# 12-Dash_Inputs.net
KiCad netlist of a schematic drawn in Altium Designer
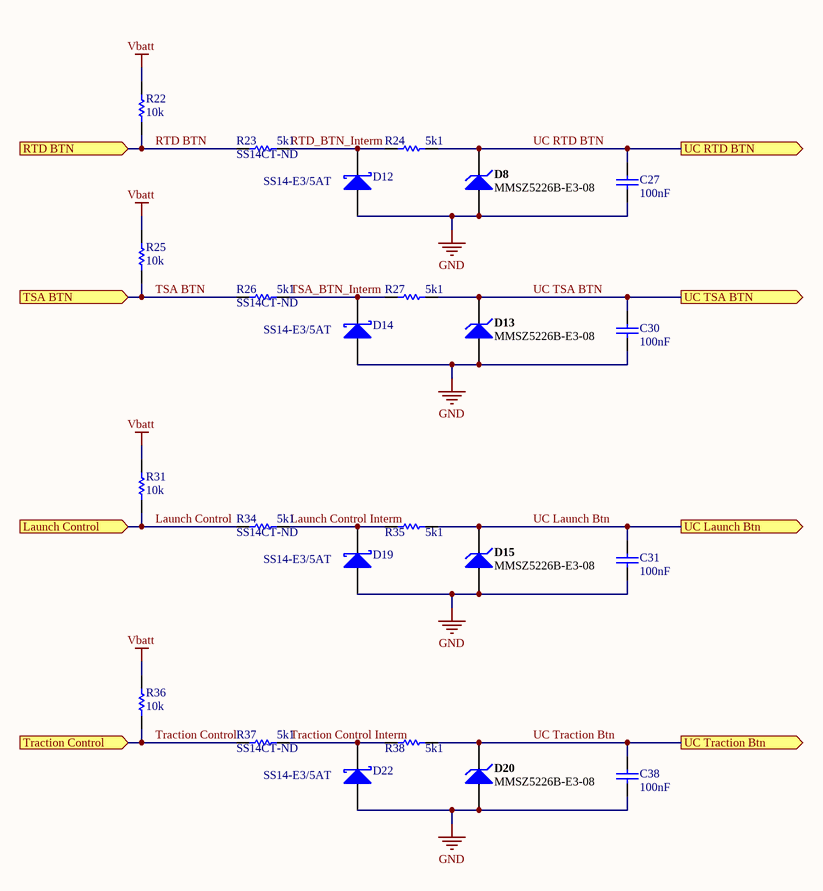
[diagram p0: 12-Dash_Inputs.SchDoc]

(export (version "E")
  (design (tool "Eeschema 10.0.6"))
  (components
    (comp (ref "C27")
      (value "100nF")
      (footprint "1608[0603]")
      (description "Capacitor")
      (fields
        (field (name "MANUFACTURER") "Yageo")
        (field (name "MANUFACTURER PART NUMBER") "CC0603KRX7R9BB104")
      )
      (libsource (lib "Miscellaneous Devices") (part "Cap"))
    )
    (comp (ref "C30")
      (value "100nF")
      (footprint "1608[0603]")
      (description "Capacitor")
      (fields
        (field (name "MANUFACTURER") "Yageo")
        (field (name "MANUFACTURER PART NUMBER") "CC0603KRX7R9BB104")
      )
      (libsource (lib "Miscellaneous Devices") (part "Cap"))
    )
    (comp (ref "C31")
      (value "100nF")
      (footprint "1608[0603]")
      (description "Capacitor")
      (fields
        (field (name "MANUFACTURER") "Yageo")
        (field (name "MANUFACTURER PART NUMBER") "CC0603KRX7R9BB104")
      )
      (libsource (lib "Miscellaneous Devices") (part "Cap"))
    )
    (comp (ref "C38")
      (value "100nF")
      (footprint "1608[0603]")
      (description "Capacitor")
      (fields
        (field (name "MANUFACTURER") "Yageo")
        (field (name "MANUFACTURER PART NUMBER") "CC0603KRX7R9BB104")
      )
      (libsource (lib "Miscellaneous Devices") (part "Cap"))
    )
    (comp (ref "D8")
      (value "MMSZ5226B-E3-08")
      (footprint "VISH-SOD-123-2_V")
      (description "Small Signal Zener Diode, 3.3 V +/- 5%, -55 to 155 degC, 2-Pin SOD-123, RoHS, Tape and Reel")
      (fields (field (name "TOLERANCE") "+/- 5%") (field (name "MANUFACTURER") "Vishay Semiconductor"))
      (libsource (lib "Altium Content Vault") (part "VISH-DZEN_A1K2-2"))
    )
    (comp (ref "D12")
      (value "SS14-E3/5AT")
      (footprint "VISH-DO-214AC-2_V")
      (fields
        (field (name "MANUFACTURER") "Vishay Semiconductor")
        (field (name "SUPPLIER PART NUMBER 1") "SS14CT-ND")
      )
      (libsource (lib "Altium Content Vault") (part "VISH-DSKY_A1K2-2"))
    )
    (comp (ref "D13")
      (value "MMSZ5226B-E3-08")
      (footprint "VISH-SOD-123-2_V")
      (description "Small Signal Zener Diode, 3.3 V +/- 5%, -55 to 155 degC, 2-Pin SOD-123, RoHS, Tape and Reel")
      (fields (field (name "TOLERANCE") "+/- 5%") (field (name "MANUFACTURER") "Vishay Semiconductor"))
      (libsource (lib "Altium Content Vault") (part "VISH-DZEN_A1K2-2"))
    )
    (comp (ref "D14")
      (value "SS14-E3/5AT")
      (footprint "VISH-DO-214AC-2_V")
      (fields
        (field (name "MANUFACTURER") "Vishay Semiconductor")
        (field (name "SUPPLIER PART NUMBER 1") "SS14CT-ND")
      )
      (libsource (lib "Altium Content Vault") (part "VISH-DSKY_A1K2-2"))
    )
    (comp (ref "D15")
      (value "MMSZ5226B-E3-08")
      (footprint "VISH-SOD-123-2_V")
      (description "Small Signal Zener Diode, 3.3 V +/- 5%, -55 to 155 degC, 2-Pin SOD-123, RoHS, Tape and Reel")
      (fields (field (name "TOLERANCE") "+/- 5%") (field (name "MANUFACTURER") "Vishay Semiconductor"))
      (libsource (lib "Altium Content Vault") (part "VISH-DZEN_A1K2-2"))
    )
    (comp (ref "D19")
      (value "SS14-E3/5AT")
      (footprint "VISH-DO-214AC-2_V")
      (fields
        (field (name "MANUFACTURER") "Vishay Semiconductor")
        (field (name "SUPPLIER PART NUMBER 1") "SS14CT-ND")
      )
      (libsource (lib "Altium Content Vault") (part "VISH-DSKY_A1K2-2"))
    )
    (comp (ref "D20")
      (value "MMSZ5226B-E3-08")
      (footprint "VISH-SOD-123-2_V")
      (description "Small Signal Zener Diode, 3.3 V +/- 5%, -55 to 155 degC, 2-Pin SOD-123, RoHS, Tape and Reel")
      (fields (field (name "TOLERANCE") "+/- 5%") (field (name "MANUFACTURER") "Vishay Semiconductor"))
      (libsource (lib "Altium Content Vault") (part "VISH-DZEN_A1K2-2"))
    )
    (comp (ref "D22")
      (value "SS14-E3/5AT")
      (footprint "VISH-DO-214AC-2_V")
      (fields
        (field (name "MANUFACTURER") "Vishay Semiconductor")
        (field (name "SUPPLIER PART NUMBER 1") "SS14CT-ND")
      )
      (libsource (lib "Altium Content Vault") (part "VISH-DSKY_A1K2-2"))
    )
    (comp (ref "R22")
      (value "10k")
      (footprint "1608[0603]")
      (description "Resistor")
      (fields
        (field (name "MANUFACTURER") "Yageo")
        (field (name "MANUFACTURER PART NUMBER") "RC0603JR-0710KL")
      )
      (libsource (lib "Miscellaneous Devices") (part "Res1"))
    )
    (comp (ref "R23")
      (value "5k1")
      (footprint "1608[0603]")
      (description "Resistor")
      (fields
        (field (name "MANUFACTURER") "Yageo")
        (field (name "MANUFACTURER PART NUMBER") "RC0603JR-075K1L")
      )
      (libsource (lib "Miscellaneous Devices") (part "Res1"))
    )
    (comp (ref "R24")
      (value "5k1")
      (footprint "1608[0603]")
      (description "Resistor")
      (fields
        (field (name "MANUFACTURER") "Yageo")
        (field (name "MANUFACTURER PART NUMBER") "RC0603JR-075K1L")
      )
      (libsource (lib "Miscellaneous Devices") (part "Res1"))
    )
    (comp (ref "R25")
      (value "10k")
      (footprint "1608[0603]")
      (description "Resistor")
      (fields
        (field (name "MANUFACTURER") "Yageo")
        (field (name "MANUFACTURER PART NUMBER") "RC0603JR-0710KL")
      )
      (libsource (lib "Miscellaneous Devices") (part "Res1"))
    )
    (comp (ref "R26")
      (value "5k1")
      (footprint "1608[0603]")
      (description "Resistor")
      (fields
        (field (name "MANUFACTURER") "Yageo")
        (field (name "MANUFACTURER PART NUMBER") "RC0603JR-075K1L")
      )
      (libsource (lib "Miscellaneous Devices") (part "Res1"))
    )
    (comp (ref "R27")
      (value "5k1")
      (footprint "1608[0603]")
      (description "Resistor")
      (fields
        (field (name "MANUFACTURER") "Yageo")
        (field (name "MANUFACTURER PART NUMBER") "RC0603JR-075K1L")
      )
      (libsource (lib "Miscellaneous Devices") (part "Res1"))
    )
    (comp (ref "R31")
      (value "10k")
      (footprint "1608[0603]")
      (description "Resistor")
      (fields
        (field (name "MANUFACTURER") "Yageo")
        (field (name "MANUFACTURER PART NUMBER") "RC0603JR-0710KL")
      )
      (libsource (lib "Miscellaneous Devices") (part "Res1"))
    )
    (comp (ref "R34")
      (value "5k1")
      (footprint "1608[0603]")
      (description "Resistor")
      (fields
        (field (name "MANUFACTURER") "Yageo")
        (field (name "MANUFACTURER PART NUMBER") "RC0603JR-075K1L")
      )
      (libsource (lib "Miscellaneous Devices") (part "Res1"))
    )
    (comp (ref "R35")
      (value "5k1")
      (footprint "1608[0603]")
      (description "Resistor")
      (fields
        (field (name "MANUFACTURER") "Yageo")
        (field (name "MANUFACTURER PART NUMBER") "RC0603JR-075K1L")
      )
      (libsource (lib "Miscellaneous Devices") (part "Res1"))
    )
    (comp (ref "R36")
      (value "10k")
      (footprint "1608[0603]")
      (description "Resistor")
      (fields
        (field (name "MANUFACTURER") "Yageo")
        (field (name "MANUFACTURER PART NUMBER") "RC0603JR-0710KL")
      )
      (libsource (lib "Miscellaneous Devices") (part "Res1"))
    )
    (comp (ref "R37")
      (value "5k1")
      (footprint "1608[0603]")
      (description "Resistor")
      (fields
        (field (name "MANUFACTURER") "Yageo")
        (field (name "MANUFACTURER PART NUMBER") "RC0603JR-075K1L")
      )
      (libsource (lib "Miscellaneous Devices") (part "Res1"))
    )
    (comp (ref "R38")
      (value "5k1")
      (footprint "1608[0603]")
      (description "Resistor")
      (fields
        (field (name "MANUFACTURER") "Yageo")
        (field (name "MANUFACTURER PART NUMBER") "RC0603JR-075K1L")
      )
      (libsource (lib "Miscellaneous Devices") (part "Res1"))
    )
  )
  (nets
    (net (code "1") (name "/Launch Control") (class "Default")
      (node (ref "R31") (pin "1") (pinfunction "1_1") (pintype "passive"))
      (node (ref "R34") (pin "1") (pinfunction "1_1") (pintype "passive"))
    )
    (net (code "2") (name "/Launch Control Interm") (class "Default")
      (node (ref "D19") (pin "2") (pinfunction "K_2") (pintype "passive"))
      (node (ref "R34") (pin "2") (pinfunction "2_2") (pintype "passive"))
      (node (ref "R35") (pin "1") (pinfunction "1_1") (pintype "passive"))
    )
    (net (code "3") (name "/RTD BTN") (class "Default")
      (node (ref "R22") (pin "1") (pinfunction "1_1") (pintype "passive"))
      (node (ref "R23") (pin "1") (pinfunction "1_1") (pintype "passive"))
    )
    (net (code "4") (name "/RTD_BTN_Interm") (class "Default")
      (node (ref "D12") (pin "2") (pinfunction "K_2") (pintype "passive"))
      (node (ref "R23") (pin "2") (pinfunction "2_2") (pintype "passive"))
      (node (ref "R24") (pin "1") (pinfunction "1_1") (pintype "passive"))
    )
    (net (code "5") (name "/TSA BTN") (class "Default")
      (node (ref "R25") (pin "1") (pinfunction "1_1") (pintype "passive"))
      (node (ref "R26") (pin "1") (pinfunction "1_1") (pintype "passive"))
    )
    (net (code "6") (name "/TSA_BTN_Interm") (class "Default")
      (node (ref "D14") (pin "2") (pinfunction "K_2") (pintype "passive"))
      (node (ref "R26") (pin "2") (pinfunction "2_2") (pintype "passive"))
      (node (ref "R27") (pin "1") (pinfunction "1_1") (pintype "passive"))
    )
    (net (code "7") (name "/Traction Control") (class "Default")
      (node (ref "R36") (pin "1") (pinfunction "1_1") (pintype "passive"))
      (node (ref "R37") (pin "1") (pinfunction "1_1") (pintype "passive"))
    )
    (net (code "8") (name "/Traction Control Interm") (class "Default")
      (node (ref "D22") (pin "2") (pinfunction "K_2") (pintype "passive"))
      (node (ref "R37") (pin "2") (pinfunction "2_2") (pintype "passive"))
      (node (ref "R38") (pin "1") (pinfunction "1_1") (pintype "passive"))
    )
    (net (code "9") (name "/UC Launch Btn") (class "Default")
      (node (ref "C31") (pin "2") (pinfunction "2_2") (pintype "passive"))
      (node (ref "D15") (pin "2") (pinfunction "K_2") (pintype "passive"))
      (node (ref "R35") (pin "2") (pinfunction "2_2") (pintype "passive"))
    )
    (net (code "10") (name "/UC RTD BTN") (class "Default")
      (node (ref "C27") (pin "2") (pinfunction "2_2") (pintype "passive"))
      (node (ref "D8") (pin "2") (pinfunction "K_2") (pintype "passive"))
      (node (ref "R24") (pin "2") (pinfunction "2_2") (pintype "passive"))
    )
    (net (code "11") (name "/UC TSA BTN") (class "Default")
      (node (ref "C30") (pin "2") (pinfunction "2_2") (pintype "passive"))
      (node (ref "D13") (pin "2") (pinfunction "K_2") (pintype "passive"))
      (node (ref "R27") (pin "2") (pinfunction "2_2") (pintype "passive"))
    )
    (net (code "12") (name "/UC Traction Btn") (class "Default")
      (node (ref "C38") (pin "2") (pinfunction "2_2") (pintype "passive"))
      (node (ref "D20") (pin "2") (pinfunction "K_2") (pintype "passive"))
      (node (ref "R38") (pin "2") (pinfunction "2_2") (pintype "passive"))
    )
    (net (code "13") (name "GND") (class "Default")
      (node (ref "C27") (pin "1") (pinfunction "1_1") (pintype "passive"))
      (node (ref "C30") (pin "1") (pinfunction "1_1") (pintype "passive"))
      (node (ref "C31") (pin "1") (pinfunction "1_1") (pintype "passive"))
      (node (ref "C38") (pin "1") (pinfunction "1_1") (pintype "passive"))
      (node (ref "D12") (pin "1") (pinfunction "A_1") (pintype "passive"))
      (node (ref "D13") (pin "1") (pinfunction "A_1") (pintype "passive"))
      (node (ref "D14") (pin "1") (pinfunction "A_1") (pintype "passive"))
      (node (ref "D15") (pin "1") (pinfunction "A_1") (pintype "passive"))
      (node (ref "D19") (pin "1") (pinfunction "A_1") (pintype "passive"))
      (node (ref "D20") (pin "1") (pinfunction "A_1") (pintype "passive"))
      (node (ref "D22") (pin "1") (pinfunction "A_1") (pintype "passive"))
      (node (ref "D8") (pin "1") (pinfunction "A_1") (pintype "passive"))
    )
    (net (code "14") (name "Vbatt") (class "Default")
      (node (ref "R22") (pin "2") (pinfunction "2_2") (pintype "passive"))
      (node (ref "R25") (pin "2") (pinfunction "2_2") (pintype "passive"))
      (node (ref "R31") (pin "2") (pinfunction "2_2") (pintype "passive"))
      (node (ref "R36") (pin "2") (pinfunction "2_2") (pintype "passive"))
    )
  )
)
